# CANInput.net
KiCad netlist of a schematic drawn in EAGLE
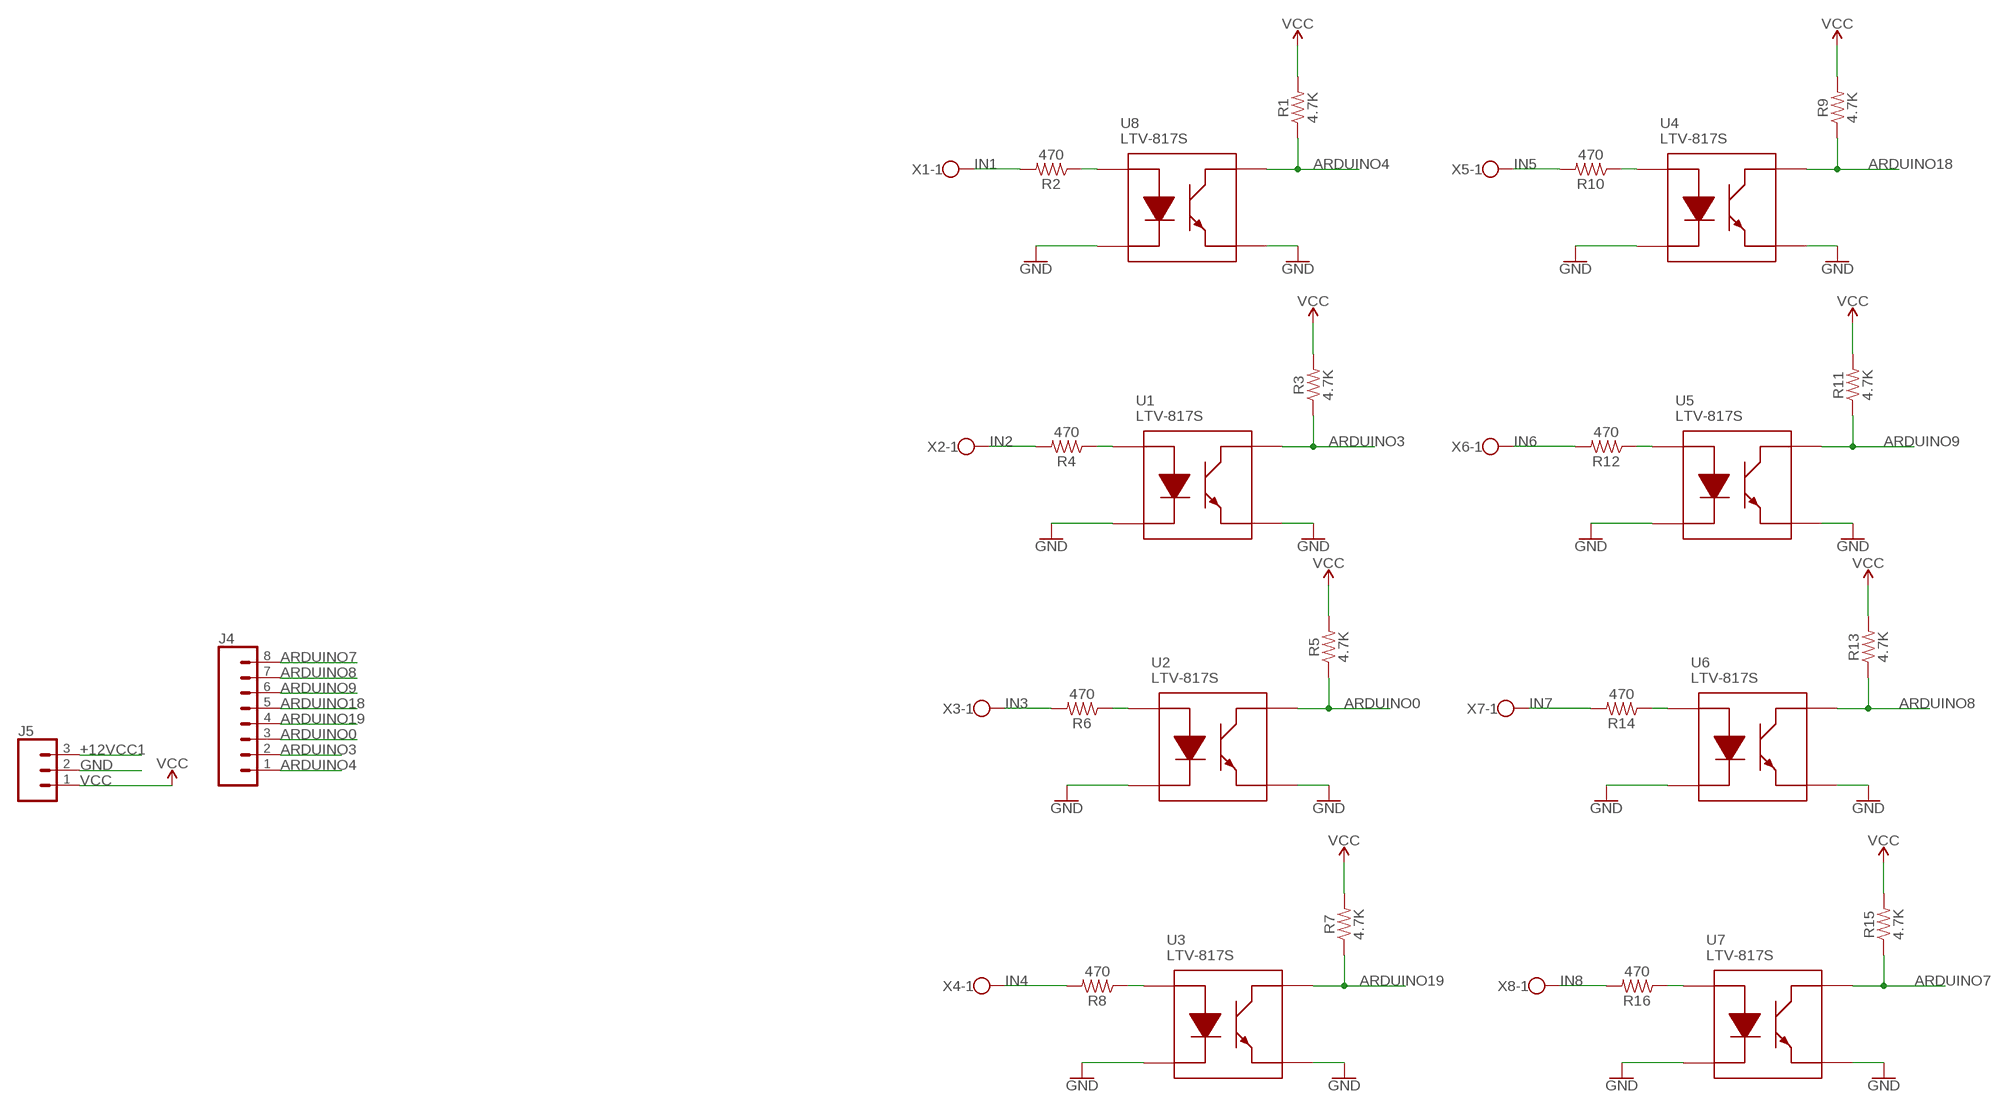
[diagram p0: schematic, sheet 1]

(export (version "E")
  (design (tool "Eeschema 10.0.6"))
  (components
    (comp (ref "J4")
      (value "CONN_08LOCK")
      (footprint "eagle-import:1X08_LOCK")
      (libsource (lib "eagle-import") (part "CONN_08LOCK"))
    )
    (comp (ref "J5")
      (value "CONN_03LOCK")
      (footprint "eagle-import:1X03_LOCK")
      (libsource (lib "eagle-import") (part "CONN_03LOCK"))
    )
    (comp (ref "R1")
      (value "4.7K")
      (footprint "eagle-import:0603")
      (libsource (lib "eagle-import") (part "1KOHM-0603-1/10W-1%"))
    )
    (comp (ref "R2")
      (value "470")
      (footprint "eagle-import:0603")
      (libsource (lib "eagle-import") (part "1KOHM-0603-1/10W-1%"))
    )
    (comp (ref "R3")
      (value "4.7K")
      (footprint "eagle-import:0603")
      (libsource (lib "eagle-import") (part "1KOHM-0603-1/10W-1%"))
    )
    (comp (ref "R4")
      (value "470")
      (footprint "eagle-import:0603")
      (libsource (lib "eagle-import") (part "1KOHM-0603-1/10W-1%"))
    )
    (comp (ref "R5")
      (value "4.7K")
      (footprint "eagle-import:0603")
      (libsource (lib "eagle-import") (part "1KOHM-0603-1/10W-1%"))
    )
    (comp (ref "R6")
      (value "470")
      (footprint "eagle-import:0603")
      (libsource (lib "eagle-import") (part "1KOHM-0603-1/10W-1%"))
    )
    (comp (ref "R7")
      (value "4.7K")
      (footprint "eagle-import:0603")
      (libsource (lib "eagle-import") (part "1KOHM-0603-1/10W-1%"))
    )
    (comp (ref "R8")
      (value "470")
      (footprint "eagle-import:0603")
      (libsource (lib "eagle-import") (part "1KOHM-0603-1/10W-1%"))
    )
    (comp (ref "R9")
      (value "4.7K")
      (footprint "eagle-import:0603")
      (libsource (lib "eagle-import") (part "1KOHM-0603-1/10W-1%"))
    )
    (comp (ref "R10")
      (value "470")
      (footprint "eagle-import:0603")
      (libsource (lib "eagle-import") (part "1KOHM-0603-1/10W-1%"))
    )
    (comp (ref "R11")
      (value "4.7K")
      (footprint "eagle-import:0603")
      (libsource (lib "eagle-import") (part "1KOHM-0603-1/10W-1%"))
    )
    (comp (ref "R12")
      (value "470")
      (footprint "eagle-import:0603")
      (libsource (lib "eagle-import") (part "1KOHM-0603-1/10W-1%"))
    )
    (comp (ref "R13")
      (value "4.7K")
      (footprint "eagle-import:0603")
      (libsource (lib "eagle-import") (part "1KOHM-0603-1/10W-1%"))
    )
    (comp (ref "R14")
      (value "470")
      (footprint "eagle-import:0603")
      (libsource (lib "eagle-import") (part "1KOHM-0603-1/10W-1%"))
    )
    (comp (ref "R15")
      (value "4.7K")
      (footprint "eagle-import:0603")
      (libsource (lib "eagle-import") (part "1KOHM-0603-1/10W-1%"))
    )
    (comp (ref "R16")
      (value "470")
      (footprint "eagle-import:0603")
      (libsource (lib "eagle-import") (part "1KOHM-0603-1/10W-1%"))
    )
    (comp (ref "U1")
      (value "LTV-817S")
      (footprint "eagle-import:SOP254P1016X460-4N")
      (fields (field (name "MOUSER_PART_NUMBER") "859-LTV-817S"))
      (libsource (lib "eagle-import") (part "LTV-817S"))
    )
    (comp (ref "U2")
      (value "LTV-817S")
      (footprint "eagle-import:SOP254P1016X460-4N")
      (fields (field (name "MOUSER_PART_NUMBER") "859-LTV-817S"))
      (libsource (lib "eagle-import") (part "LTV-817S"))
    )
    (comp (ref "U3")
      (value "LTV-817S")
      (footprint "eagle-import:SOP254P1016X460-4N")
      (fields (field (name "MOUSER_PART_NUMBER") "859-LTV-817S"))
      (libsource (lib "eagle-import") (part "LTV-817S"))
    )
    (comp (ref "U4")
      (value "LTV-817S")
      (footprint "eagle-import:SOP254P1016X460-4N")
      (fields (field (name "MOUSER_PART_NUMBER") "859-LTV-817S"))
      (libsource (lib "eagle-import") (part "LTV-817S"))
    )
    (comp (ref "U5")
      (value "LTV-817S")
      (footprint "eagle-import:SOP254P1016X460-4N")
      (fields (field (name "MOUSER_PART_NUMBER") "859-LTV-817S"))
      (libsource (lib "eagle-import") (part "LTV-817S"))
    )
    (comp (ref "U6")
      (value "LTV-817S")
      (footprint "eagle-import:SOP254P1016X460-4N")
      (fields (field (name "MOUSER_PART_NUMBER") "859-LTV-817S"))
      (libsource (lib "eagle-import") (part "LTV-817S"))
    )
    (comp (ref "U7")
      (value "LTV-817S")
      (footprint "eagle-import:SOP254P1016X460-4N")
      (fields (field (name "MOUSER_PART_NUMBER") "859-LTV-817S"))
      (libsource (lib "eagle-import") (part "LTV-817S"))
    )
    (comp (ref "U8")
      (value "LTV-817S")
      (footprint "eagle-import:SOP254P1016X460-4N")
      (fields (field (name "MOUSER_PART_NUMBER") "859-LTV-817S"))
      (libsource (lib "eagle-import") (part "LTV-817S"))
    )
    (comp (ref "X1")
      (value "W237-102")
      (footprint "eagle-import:W237-102")
      (fields (field (name "MPN") "237-102"))
      (libsource (lib "eagle-import") (part "W237-102"))
    )
    (comp (ref "X2")
      (value "W237-102")
      (footprint "eagle-import:W237-102")
      (fields (field (name "MPN") "237-102"))
      (libsource (lib "eagle-import") (part "W237-102"))
    )
    (comp (ref "X3")
      (value "W237-102")
      (footprint "eagle-import:W237-102")
      (fields (field (name "MPN") "237-102"))
      (libsource (lib "eagle-import") (part "W237-102"))
    )
    (comp (ref "X4")
      (value "W237-102")
      (footprint "eagle-import:W237-102")
      (fields (field (name "MPN") "237-102"))
      (libsource (lib "eagle-import") (part "W237-102"))
    )
    (comp (ref "X5")
      (value "W237-102")
      (footprint "eagle-import:W237-102")
      (fields (field (name "MPN") "237-102"))
      (libsource (lib "eagle-import") (part "W237-102"))
    )
    (comp (ref "X6")
      (value "W237-102")
      (footprint "eagle-import:W237-102")
      (fields (field (name "MPN") "237-102"))
      (libsource (lib "eagle-import") (part "W237-102"))
    )
    (comp (ref "X7")
      (value "W237-102")
      (footprint "eagle-import:W237-102")
      (fields (field (name "MPN") "237-102"))
      (libsource (lib "eagle-import") (part "W237-102"))
    )
    (comp (ref "X8")
      (value "W237-102")
      (footprint "eagle-import:W237-102")
      (fields (field (name "MPN") "237-102"))
      (libsource (lib "eagle-import") (part "W237-102"))
    )
  )
  (nets
    (net (code "1") (name "/+12VCC1") (class "Default")
      (node (ref "J5") (pin "3") (pinfunction "3_3") (pintype "passive"))
    )
    (net (code "2") (name "/ARDUINO0") (class "Default")
      (node (ref "J4") (pin "3") (pinfunction "3_3") (pintype "passive"))
      (node (ref "R5") (pin "1") (pinfunction "1_1") (pintype "passive"))
      (node (ref "U2") (pin "4") (pinfunction "COLLECTOR_4") (pintype "bidirectional"))
    )
    (net (code "3") (name "/ARDUINO3") (class "Default")
      (node (ref "J4") (pin "2") (pinfunction "2_2") (pintype "passive"))
      (node (ref "R3") (pin "1") (pinfunction "1_1") (pintype "passive"))
      (node (ref "U1") (pin "4") (pinfunction "COLLECTOR_4") (pintype "bidirectional"))
    )
    (net (code "4") (name "/ARDUINO4") (class "Default")
      (node (ref "J4") (pin "1") (pinfunction "1_1") (pintype "passive"))
      (node (ref "R1") (pin "1") (pinfunction "1_1") (pintype "passive"))
      (node (ref "U8") (pin "4") (pinfunction "COLLECTOR_4") (pintype "bidirectional"))
    )
    (net (code "5") (name "/ARDUINO7") (class "Default")
      (node (ref "J4") (pin "8") (pinfunction "8_8") (pintype "passive"))
      (node (ref "R15") (pin "1") (pinfunction "1_1") (pintype "passive"))
      (node (ref "U7") (pin "4") (pinfunction "COLLECTOR_4") (pintype "bidirectional"))
    )
    (net (code "6") (name "/ARDUINO8") (class "Default")
      (node (ref "J4") (pin "7") (pinfunction "7_7") (pintype "passive"))
      (node (ref "R13") (pin "1") (pinfunction "1_1") (pintype "passive"))
      (node (ref "U6") (pin "4") (pinfunction "COLLECTOR_4") (pintype "bidirectional"))
    )
    (net (code "7") (name "/ARDUINO9") (class "Default")
      (node (ref "J4") (pin "6") (pinfunction "6_6") (pintype "passive"))
      (node (ref "R11") (pin "1") (pinfunction "1_1") (pintype "passive"))
      (node (ref "U5") (pin "4") (pinfunction "COLLECTOR_4") (pintype "bidirectional"))
    )
    (net (code "8") (name "/ARDUINO18") (class "Default")
      (node (ref "J4") (pin "5") (pinfunction "5_5") (pintype "passive"))
      (node (ref "R9") (pin "1") (pinfunction "1_1") (pintype "passive"))
      (node (ref "U4") (pin "4") (pinfunction "COLLECTOR_4") (pintype "bidirectional"))
    )
    (net (code "9") (name "/ARDUINO19") (class "Default")
      (node (ref "J4") (pin "4") (pinfunction "4_4") (pintype "passive"))
      (node (ref "R7") (pin "1") (pinfunction "1_1") (pintype "passive"))
      (node (ref "U3") (pin "4") (pinfunction "COLLECTOR_4") (pintype "bidirectional"))
    )
    (net (code "10") (name "/IN1") (class "Default")
      (node (ref "R2") (pin "2") (pinfunction "2_2") (pintype "passive"))
      (node (ref "X1") (pin "1") (pinfunction "KL_1") (pintype "passive"))
    )
    (net (code "11") (name "/IN2") (class "Default")
      (node (ref "R4") (pin "2") (pinfunction "2_2") (pintype "passive"))
      (node (ref "X2") (pin "1") (pinfunction "KL_1") (pintype "passive"))
    )
    (net (code "12") (name "/IN3") (class "Default")
      (node (ref "R6") (pin "2") (pinfunction "2_2") (pintype "passive"))
      (node (ref "X3") (pin "1") (pinfunction "KL_1") (pintype "passive"))
    )
    (net (code "13") (name "/IN4") (class "Default")
      (node (ref "R8") (pin "2") (pinfunction "2_2") (pintype "passive"))
      (node (ref "X4") (pin "1") (pinfunction "KL_1") (pintype "passive"))
    )
    (net (code "14") (name "/IN5") (class "Default")
      (node (ref "R10") (pin "2") (pinfunction "2_2") (pintype "passive"))
      (node (ref "X5") (pin "1") (pinfunction "KL_1") (pintype "passive"))
    )
    (net (code "15") (name "/IN6") (class "Default")
      (node (ref "R12") (pin "2") (pinfunction "2_2") (pintype "passive"))
      (node (ref "X6") (pin "1") (pinfunction "KL_1") (pintype "passive"))
    )
    (net (code "16") (name "/IN7") (class "Default")
      (node (ref "R14") (pin "2") (pinfunction "2_2") (pintype "passive"))
      (node (ref "X7") (pin "1") (pinfunction "KL_1") (pintype "passive"))
    )
    (net (code "17") (name "/IN8") (class "Default")
      (node (ref "R16") (pin "2") (pinfunction "2_2") (pintype "passive"))
      (node (ref "X8") (pin "1") (pinfunction "KL_1") (pintype "passive"))
    )
    (net (code "18") (name "GND") (class "Default")
      (node (ref "J5") (pin "2") (pinfunction "2_2") (pintype "passive"))
      (node (ref "U1") (pin "2") (pinfunction "CATHODE_2") (pintype "bidirectional"))
      (node (ref "U1") (pin "3") (pinfunction "EMITTER_3") (pintype "bidirectional"))
      (node (ref "U2") (pin "2") (pinfunction "CATHODE_2") (pintype "bidirectional"))
      (node (ref "U2") (pin "3") (pinfunction "EMITTER_3") (pintype "bidirectional"))
      (node (ref "U3") (pin "2") (pinfunction "CATHODE_2") (pintype "bidirectional"))
      (node (ref "U3") (pin "3") (pinfunction "EMITTER_3") (pintype "bidirectional"))
      (node (ref "U4") (pin "2") (pinfunction "CATHODE_2") (pintype "bidirectional"))
      (node (ref "U4") (pin "3") (pinfunction "EMITTER_3") (pintype "bidirectional"))
      (node (ref "U5") (pin "2") (pinfunction "CATHODE_2") (pintype "bidirectional"))
      (node (ref "U5") (pin "3") (pinfunction "EMITTER_3") (pintype "bidirectional"))
      (node (ref "U6") (pin "2") (pinfunction "CATHODE_2") (pintype "bidirectional"))
      (node (ref "U6") (pin "3") (pinfunction "EMITTER_3") (pintype "bidirectional"))
      (node (ref "U7") (pin "2") (pinfunction "CATHODE_2") (pintype "bidirectional"))
      (node (ref "U7") (pin "3") (pinfunction "EMITTER_3") (pintype "bidirectional"))
      (node (ref "U8") (pin "2") (pinfunction "CATHODE_2") (pintype "bidirectional"))
      (node (ref "U8") (pin "3") (pinfunction "EMITTER_3") (pintype "bidirectional"))
    )
    (net (code "19") (name "Net-(U1-ANODE)") (class "Default")
      (node (ref "R4") (pin "1") (pinfunction "1_1") (pintype "passive"))
      (node (ref "U1") (pin "1") (pinfunction "ANODE_1") (pintype "bidirectional"))
    )
    (net (code "20") (name "Net-(U2-ANODE)") (class "Default")
      (node (ref "R6") (pin "1") (pinfunction "1_1") (pintype "passive"))
      (node (ref "U2") (pin "1") (pinfunction "ANODE_1") (pintype "bidirectional"))
    )
    (net (code "21") (name "Net-(U3-ANODE)") (class "Default")
      (node (ref "R8") (pin "1") (pinfunction "1_1") (pintype "passive"))
      (node (ref "U3") (pin "1") (pinfunction "ANODE_1") (pintype "bidirectional"))
    )
    (net (code "22") (name "Net-(U4-ANODE)") (class "Default")
      (node (ref "R10") (pin "1") (pinfunction "1_1") (pintype "passive"))
      (node (ref "U4") (pin "1") (pinfunction "ANODE_1") (pintype "bidirectional"))
    )
    (net (code "23") (name "Net-(U5-ANODE)") (class "Default")
      (node (ref "R12") (pin "1") (pinfunction "1_1") (pintype "passive"))
      (node (ref "U5") (pin "1") (pinfunction "ANODE_1") (pintype "bidirectional"))
    )
    (net (code "24") (name "Net-(U6-ANODE)") (class "Default")
      (node (ref "R14") (pin "1") (pinfunction "1_1") (pintype "passive"))
      (node (ref "U6") (pin "1") (pinfunction "ANODE_1") (pintype "bidirectional"))
    )
    (net (code "25") (name "Net-(U7-ANODE)") (class "Default")
      (node (ref "R16") (pin "1") (pinfunction "1_1") (pintype "passive"))
      (node (ref "U7") (pin "1") (pinfunction "ANODE_1") (pintype "bidirectional"))
    )
    (net (code "26") (name "Net-(U8-ANODE)") (class "Default")
      (node (ref "R2") (pin "1") (pinfunction "1_1") (pintype "passive"))
      (node (ref "U8") (pin "1") (pinfunction "ANODE_1") (pintype "bidirectional"))
    )
    (net (code "27") (name "VCC") (class "Default")
      (node (ref "J5") (pin "1") (pinfunction "1_1") (pintype "passive"))
      (node (ref "R1") (pin "2") (pinfunction "2_2") (pintype "passive"))
      (node (ref "R11") (pin "2") (pinfunction "2_2") (pintype "passive"))
      (node (ref "R13") (pin "2") (pinfunction "2_2") (pintype "passive"))
      (node (ref "R15") (pin "2") (pinfunction "2_2") (pintype "passive"))
      (node (ref "R3") (pin "2") (pinfunction "2_2") (pintype "passive"))
      (node (ref "R5") (pin "2") (pinfunction "2_2") (pintype "passive"))
      (node (ref "R7") (pin "2") (pinfunction "2_2") (pintype "passive"))
      (node (ref "R9") (pin "2") (pinfunction "2_2") (pintype "passive"))
    )
  )
)
